# ProtectionChannelD.net
KiCad netlist of a schematic drawn in Altium Designer
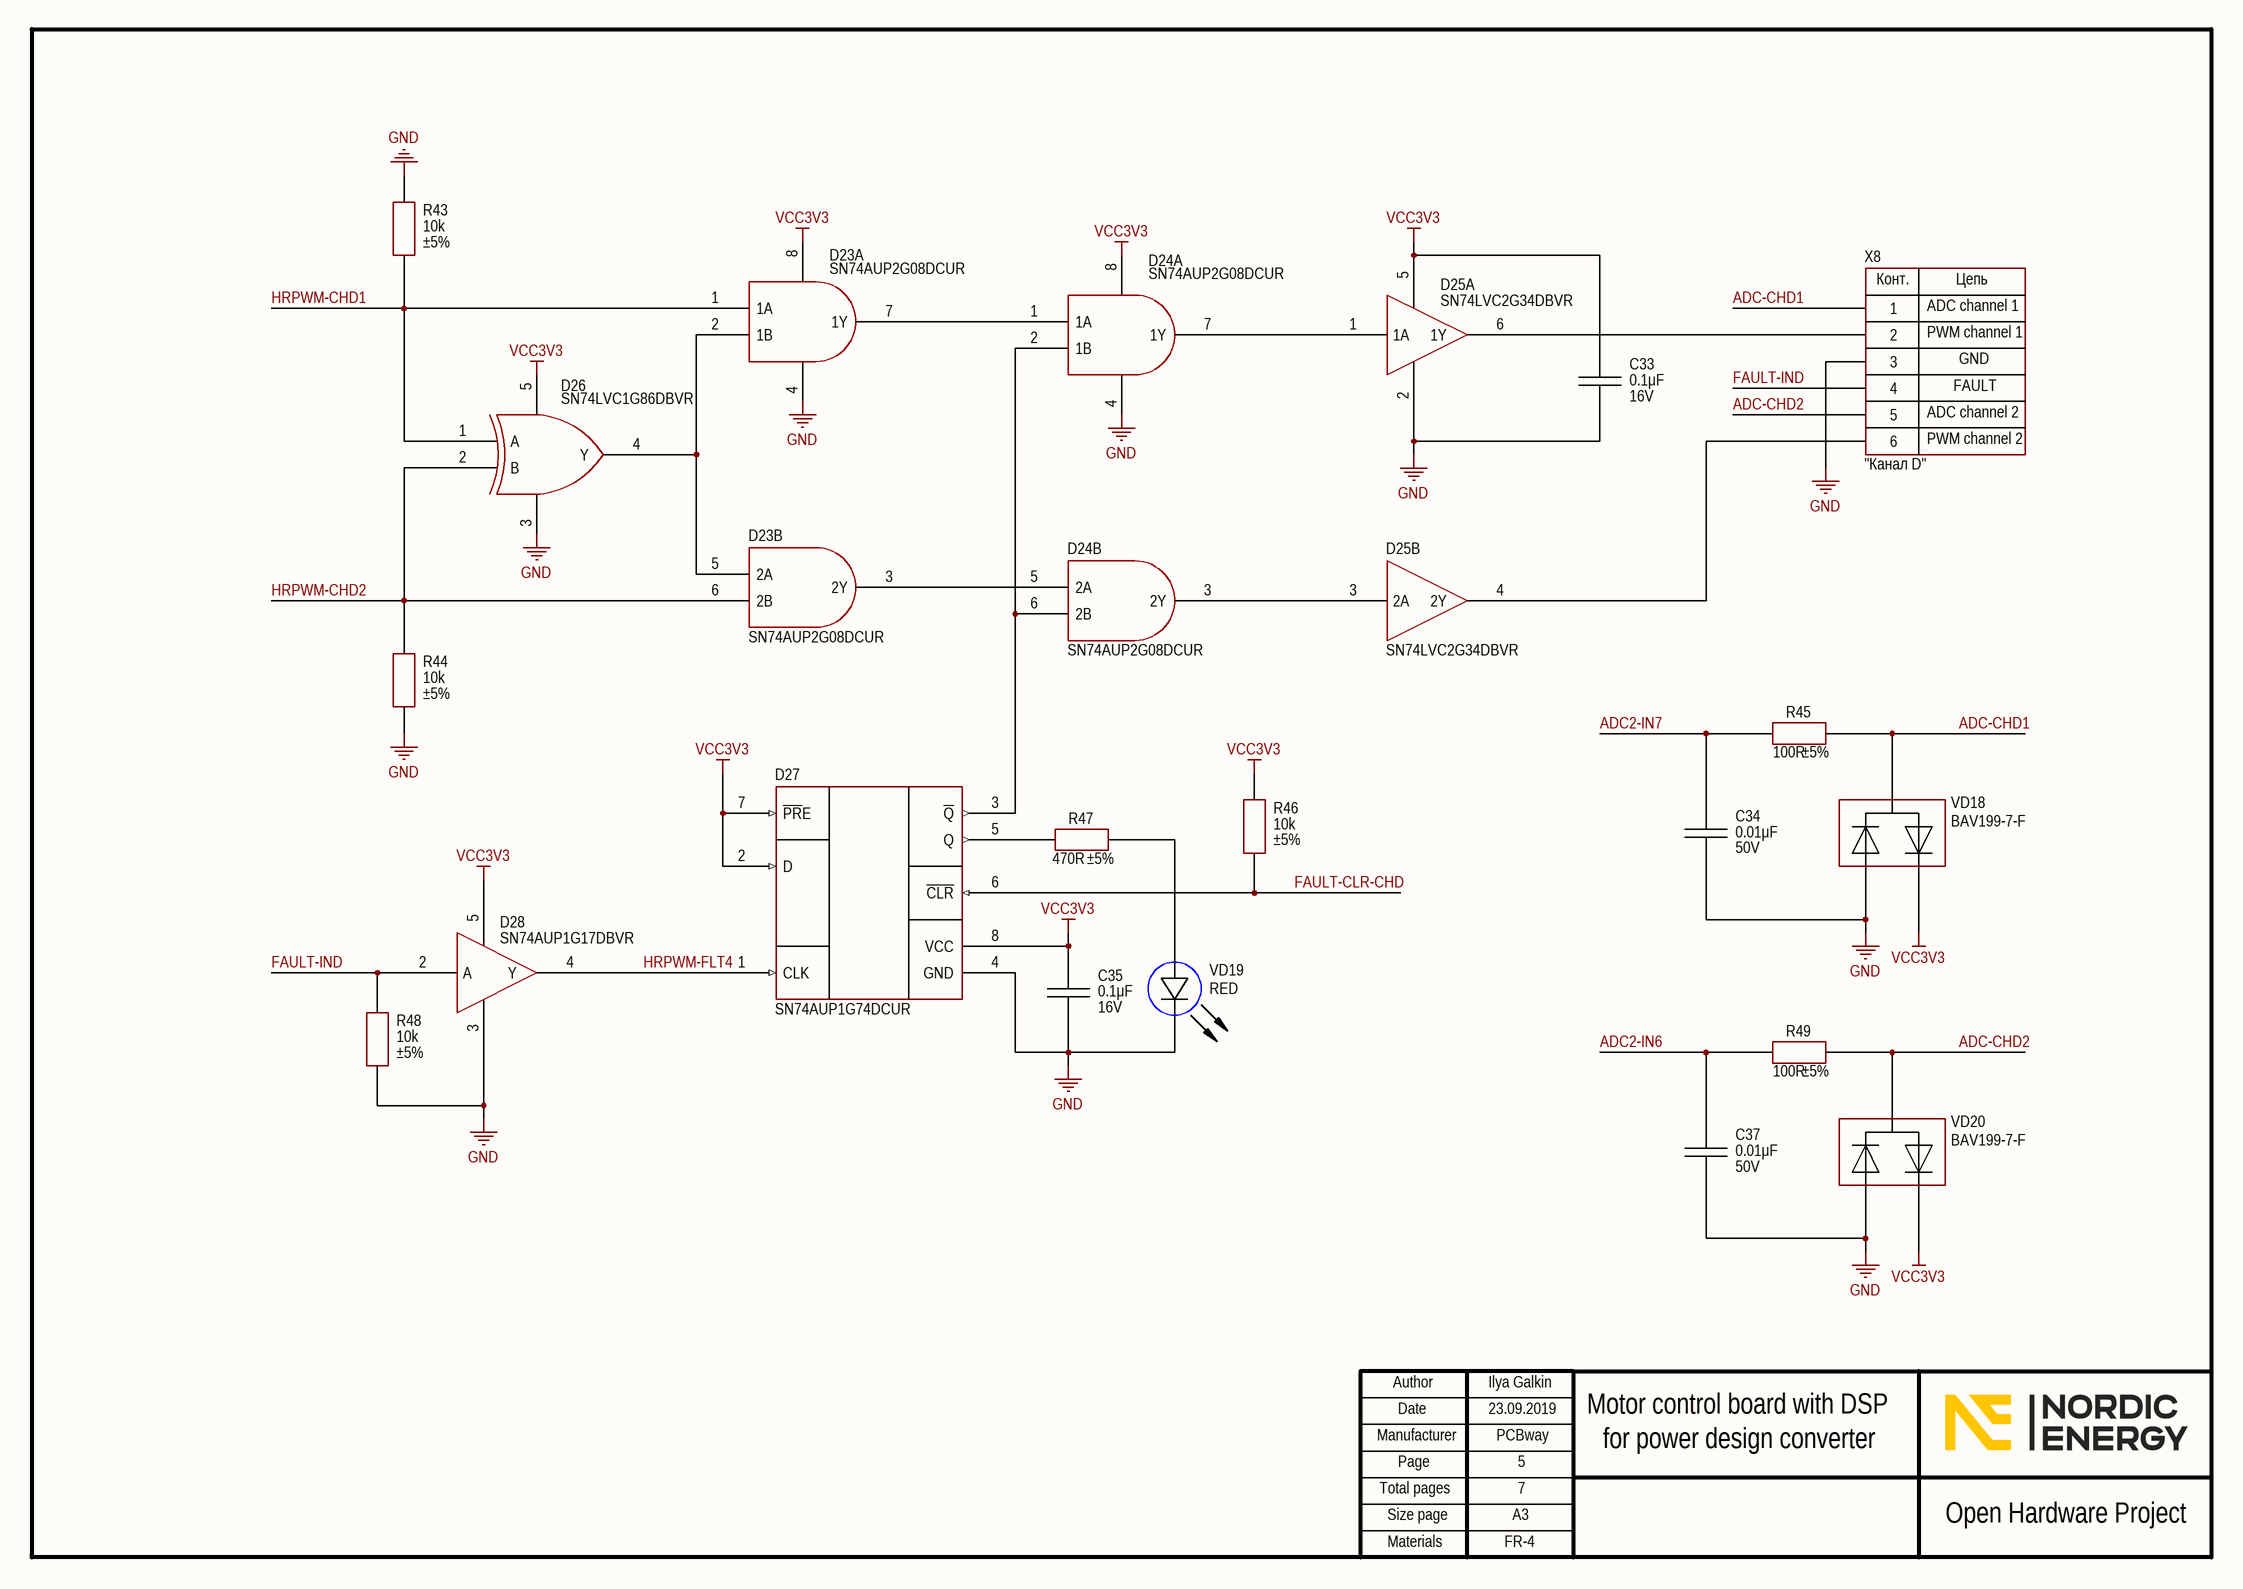
[diagram p0: ProtectionChannelD.SchDoc]

(export (version "E")
  (design (tool "Eeschema 10.0.6"))
  (components
    (comp (ref "C33")
      (value "0.1μF")
      (footprint "CAP: 0805")
      (fields
        (field (name "MANUFACTURER") "Yageo")
        (field (name "PARTNUMBER") "CC0805KRX7R7BB104")
        (field (name "VALUEMANUFACTURERPARTNUMBER") "Ceramic capacitor, 0.1μF, X7R, ±10%, 16V, 0805, -55...+125°C")
        (field (name "VOLTAGE") "16V")
      )
      (libsource (lib "Capacitor") (part "Ceramic_0805"))
    )
    (comp (ref "C34")
      (value "0.01μF")
      (footprint "CAP: 0805")
      (fields
        (field (name "MANUFACTURER") "Yageo")
        (field (name "PARTNUMBER") "CC0805KRX7R9BB103")
        (field (name "VALUEMANUFACTURERPARTNUMBER") "Ceramic capacitor, 0.01μF, X7R, ±10%, 50V, 0805, -55...+125°C")
        (field (name "VOLTAGE") "50V")
      )
      (libsource (lib "Capacitor") (part "Ceramic_0805"))
    )
    (comp (ref "C35")
      (value "0.1μF")
      (footprint "CAP: 0805")
      (fields
        (field (name "MANUFACTURER") "Yageo")
        (field (name "PARTNUMBER") "CC0805KRX7R7BB104")
        (field (name "VALUEMANUFACTURERPARTNUMBER") "Ceramic capacitor, 0.1μF, X7R, ±10%, 16V, 0805, -55...+125°C")
        (field (name "VOLTAGE") "16V")
      )
      (libsource (lib "Capacitor") (part "Ceramic_0805"))
    )
    (comp (ref "C37")
      (value "0.01μF")
      (footprint "CAP: 0805")
      (fields
        (field (name "MANUFACTURER") "Yageo")
        (field (name "PARTNUMBER") "CC0805KRX7R9BB103")
        (field (name "VALUEMANUFACTURERPARTNUMBER") "Ceramic capacitor, 0.01μF, X7R, ±10%, 50V, 0805, -55...+125°C")
        (field (name "VOLTAGE") "50V")
      )
      (libsource (lib "Capacitor") (part "Ceramic_0805"))
    )
    (comp (ref "D23")
      (value "~")
      (footprint "8-VSSOP")
      (description "AND")
      (fields
        (field (name "MANUFACTURER") "Texas Instruments")
        (field (name "VALUEMANUFACTURERPARTNUMBER") "IC logic AND, 0.8...3.6V, -40...+855°C, 8-VSSOP")
        (field (name "PARTNUMBER") "SN74AUP2G08DCUR")
      )
      (libsource (lib "IC. Logic") (part "SN74AUP2G08DCUR"))
    )
    (comp (ref "D24")
      (value "~")
      (footprint "8-VSSOP")
      (description "AND")
      (fields
        (field (name "MANUFACTURER") "Texas Instruments")
        (field (name "VALUEMANUFACTURERPARTNUMBER") "IC logic AND, 0.8...3.6V, -40...+855°C, 8-VSSOP")
        (field (name "PARTNUMBER") "SN74AUP2G08DCUR")
      )
      (libsource (lib "IC. Logic") (part "SN74AUP2G08DCUR"))
    )
    (comp (ref "D25")
      (value "~")
      (footprint "SOT23-6")
      (description "Buffer")
      (fields
        (field (name "MANUFACTURER") "Texas Instruments")
        (field (name "VALUEMANUFACTURERPARTNUMBER") "IC logic buffer, 1.65...5.5V, -40...+125°C, SOT23-6")
        (field (name "PARTNUMBER") "SN74LVC2G34DBVR")
      )
      (libsource (lib "IC. Logic") (part "SN74LVC2G34DBVR"))
    )
    (comp (ref "D26")
      (value "~")
      (footprint "SOT23-5")
      (description "XOR")
      (fields
        (field (name "MANUFACTURER") "Texas Instruments")
        (field (name "VALUEMANUFACTURERPARTNUMBER") "IC logic XOR, 1.65...5.5V, -40...+125°C, SOT23-5")
        (field (name "PARTNUMBER") "SN74LVC1G86DBVR")
      )
      (libsource (lib "IC. Logic") (part "SN74LVC1G86DBVR"))
    )
    (comp (ref "D27")
      (value "~")
      (footprint "8-VSSOP")
      (description "D-trigger")
      (fields
        (field (name "MANUFACTURER") "Texas Instruments")
        (field (name "VALUEMANUFACTURERPARTNUMBER") "ICtrigger D-type, 0.8...3.6V, -40...+85°C, 8-VSSOP")
        (field (name "PARTNUMBER") "SN74AUP1G74DCUR")
      )
      (libsource (lib "IC. Logic") (part "SN74AUP1G74DCUR"))
    )
    (comp (ref "D28")
      (value "~")
      (footprint "SOT23-5")
      (description "Schmitt trigger")
      (fields
        (field (name "MANUFACTURER") "Texas Instruments")
        (field (name "VALUEMANUFACTURERPARTNUMBER") "IC Schmitt trigger, 0.8...3.6V, -40...+85°C, SOT23-6")
        (field (name "PARTNUMBER") "SN74AUP1G17DBVR")
      )
      (libsource (lib "IC. Logic") (part "SN74AUP1G17DBVR"))
    )
    (comp (ref "R43")
      (value "10k")
      (footprint "RES: 0805")
      (fields
        (field (name "MANUFACTURER") "Yageo")
        (field (name "PARTNUMBER") "RC0805JR-0710KL")
        (field (name "VALUEMANUFACTURERPARTNUMBER") "Resistor film, 10k, ±5%, 0805, 0.125W, -55...+125°C")
        (field (name "TOLERANCE") "±5%")
      )
      (libsource (lib "Resistor") (part "Resistor_0805"))
    )
    (comp (ref "R44")
      (value "10k")
      (footprint "RES: 0805")
      (fields
        (field (name "MANUFACTURER") "Yageo")
        (field (name "PARTNUMBER") "RC0805JR-0710KL")
        (field (name "VALUEMANUFACTURERPARTNUMBER") "Resistor film, 10k, ±5%, 0805, 0.125W, -55...+125°C")
        (field (name "TOLERANCE") "±5%")
      )
      (libsource (lib "Resistor") (part "Resistor_0805"))
    )
    (comp (ref "R45")
      (value "100R")
      (footprint "RES: 0805")
      (fields
        (field (name "MANUFACTURER") "Yageo")
        (field (name "PARTNUMBER") "RC0805JR-07100RL")
        (field (name "VALUEMANUFACTURERPARTNUMBER") "Resistor film, 100R, ±5%, 0805, 0.125W, -55...+125°C")
        (field (name "TOLERANCE") "±5%")
      )
      (libsource (lib "") (part "Resistor_0805_1"))
    )
    (comp (ref "R46")
      (value "10k")
      (footprint "RES: 0805")
      (fields
        (field (name "MANUFACTURER") "Yageo")
        (field (name "PARTNUMBER") "RC0805JR-0710KL")
        (field (name "VALUEMANUFACTURERPARTNUMBER") "Resistor film, 10k, ±5%, 0805, 0.125W, -55...+125°C")
        (field (name "TOLERANCE") "±5%")
      )
      (libsource (lib "Resistor") (part "Resistor_0805"))
    )
    (comp (ref "R47")
      (value "470R")
      (footprint "RES: 0805")
      (fields
        (field (name "MANUFACTURER") "Yageo")
        (field (name "PARTNUMBER") "RC0805JR-07470RL")
        (field (name "VALUEMANUFACTURERPARTNUMBER") "Resistor film, 470R, ±5%, 0805, 0.125W, -55...+125°C")
        (field (name "TOLERANCE") "±5%")
      )
      (libsource (lib "") (part "Resistor_0805_2"))
    )
    (comp (ref "R48")
      (value "10k")
      (footprint "RES: 0805")
      (fields
        (field (name "MANUFACTURER") "Yageo")
        (field (name "PARTNUMBER") "RC0805JR-0710KL")
        (field (name "VALUEMANUFACTURERPARTNUMBER") "Resistor film, 10k, ±5%, 0805, 0.125W, -55...+125°C")
        (field (name "TOLERANCE") "±5%")
      )
      (libsource (lib "Resistor") (part "Resistor_0805"))
    )
    (comp (ref "R49")
      (value "100R")
      (footprint "RES: 0805")
      (fields
        (field (name "MANUFACTURER") "Yageo")
        (field (name "PARTNUMBER") "RC0805JR-07100RL")
        (field (name "VALUEMANUFACTURERPARTNUMBER") "Resistor film, 100R, ±5%, 0805, 0.125W, -55...+125°C")
        (field (name "TOLERANCE") "±5%")
      )
      (libsource (lib "") (part "Resistor_0805_1"))
    )
    (comp (ref "VD18")
      (value "~")
      (footprint "SOT23")
      (fields
        (field (name "MANUFACTURER") "Diodes Incorporated")
        (field (name "VALUEMANUFACTURERPARTNUMBER") "Diode array, 85V, 140mA, 1.1V, 3us, SOT-23, -65...+150°C")
        (field (name "VOLTAGE") "85V")
        (field (name "PARTNUMBER") "BAV199-7-F")
      )
      (libsource (lib "Diode") (part "Diode_array"))
    )
    (comp (ref "VD19")
      (value "~")
      (footprint "LED: 0805R")
      (fields
        (field (name "MANUFACTURER") "Wurth")
        (field (name "VALUEMANUFACTURERPARTNUMBER") "LED, 20mA, 2V, 0805, -55...+150°C")
        (field (name "PARTNUMBER") "150080RS75000")
        (field (name "COLOR") "RED")
      )
      (libsource (lib "Diode") (part "LED_single"))
    )
    (comp (ref "VD20")
      (value "~")
      (footprint "SOT23")
      (fields
        (field (name "MANUFACTURER") "Diodes Incorporated")
        (field (name "VALUEMANUFACTURERPARTNUMBER") "Diode array, 85V, 140mA, 1.1V, 3us, SOT-23, -65...+150°C")
        (field (name "VOLTAGE") "85V")
        (field (name "PARTNUMBER") "BAV199-7-F")
      )
      (libsource (lib "Diode") (part "Diode_array"))
    )
    (comp (ref "X8")
      (value "~")
      (footprint "CON: PLD-6")
      (fields
        (field (name "MANUFACTURER") "Connfly")
        (field (name "VALUEMANUFACTURERPARTNUMBER") "Connector, 6pin, 2.54mm, 500VAC, 3A")
        (field (name "PARTNUMBER") "PLD-6")
        (field (name "COMMENTTEXT") "\"Канал D\"")
      )
      (libsource (lib "Connector") (part "PLD-6"))
    )
  )
  (nets
    (net (code "1") (name "/ADC-CHD1") (class "Default")
      (node (ref "R45") (pin "2") (pinfunction "2_2") (pintype "passive"))
      (node (ref "VD18") (pin "3") (pinfunction "3_3") (pintype "passive"))
      (node (ref "X8") (pin "1") (pinfunction "1_1") (pintype "passive"))
    )
    (net (code "2") (name "/ADC-CHD2") (class "Default")
      (node (ref "R49") (pin "2") (pinfunction "2_2") (pintype "passive"))
      (node (ref "VD20") (pin "3") (pinfunction "3_3") (pintype "passive"))
      (node (ref "X8") (pin "5") (pinfunction "5_5") (pintype "power_in"))
    )
    (net (code "3") (name "/ADC2-IN6") (class "Default")
      (node (ref "C37") (pin "2") (pinfunction "2_2") (pintype "power_in"))
      (node (ref "R49") (pin "1") (pinfunction "1_1") (pintype "passive"))
    )
    (net (code "4") (name "/ADC2-IN7") (class "Default")
      (node (ref "C34") (pin "2") (pinfunction "2_2") (pintype "power_in"))
      (node (ref "R45") (pin "1") (pinfunction "1_1") (pintype "passive"))
    )
    (net (code "5") (name "/FAULT-CLR-CHD") (class "Default")
      (node (ref "D27") (pin "6") (pinfunction "~{CLR}_6") (pintype "input"))
      (node (ref "R46") (pin "2") (pinfunction "2_2") (pintype "passive"))
    )
    (net (code "6") (name "/FAULT-IND") (class "Default")
      (node (ref "D28") (pin "2") (pinfunction "A_2") (pintype "passive"))
      (node (ref "R48") (pin "1") (pinfunction "1_1") (pintype "passive"))
      (node (ref "X8") (pin "4") (pinfunction "4_4") (pintype "power_in"))
    )
    (net (code "7") (name "/HRPWM-CHD1") (class "Default")
      (node (ref "D23") (pin "1") (pinfunction "1A_1") (pintype "passive"))
      (node (ref "D26") (pin "1") (pinfunction "A_1") (pintype "passive"))
      (node (ref "R43") (pin "2") (pinfunction "2_2") (pintype "passive"))
    )
    (net (code "8") (name "/HRPWM-CHD2") (class "Default")
      (node (ref "D23") (pin "6") (pinfunction "2B_6") (pintype "passive"))
      (node (ref "D26") (pin "2") (pinfunction "B_2") (pintype "passive"))
      (node (ref "R44") (pin "1") (pinfunction "1_1") (pintype "passive"))
    )
    (net (code "9") (name "/HRPWM-FLT4") (class "Default")
      (node (ref "D27") (pin "1") (pinfunction "CLK_1") (pintype "input"))
      (node (ref "D28") (pin "4") (pinfunction "Y_4") (pintype "passive"))
    )
    (net (code "10") (name "GND") (class "Default")
      (node (ref "C33") (pin "1") (pinfunction "1_1") (pintype "power_in"))
      (node (ref "C34") (pin "1") (pinfunction "1_1") (pintype "power_in"))
      (node (ref "C35") (pin "1") (pinfunction "1_1") (pintype "power_in"))
      (node (ref "C37") (pin "1") (pinfunction "1_1") (pintype "power_in"))
      (node (ref "D23") (pin "4") (pintype "passive"))
      (node (ref "D24") (pin "4") (pintype "passive"))
      (node (ref "D25") (pin "2") (pintype "passive"))
      (node (ref "D26") (pin "3") (pintype "passive"))
      (node (ref "D27") (pin "4") (pinfunction "GND_4") (pintype "passive"))
      (node (ref "D28") (pin "3") (pintype "passive"))
      (node (ref "R43") (pin "1") (pinfunction "1_1") (pintype "passive"))
      (node (ref "R44") (pin "2") (pinfunction "2_2") (pintype "passive"))
      (node (ref "R48") (pin "2") (pinfunction "2_2") (pintype "passive"))
      (node (ref "VD18") (pin "1") (pinfunction "1_1") (pintype "passive"))
      (node (ref "VD19") (pin "2") (pinfunction "C_2") (pintype "passive"))
      (node (ref "VD20") (pin "1") (pinfunction "1_1") (pintype "passive"))
      (node (ref "X8") (pin "3") (pinfunction "3_3") (pintype "power_in"))
    )
    (net (code "11") (name "Net-(D23A-1B)") (class "Default")
      (node (ref "D23") (pin "2") (pinfunction "1B_2") (pintype "passive"))
      (node (ref "D23") (pin "5") (pinfunction "2A_5") (pintype "passive"))
      (node (ref "D26") (pin "4") (pinfunction "Y_4") (pintype "passive"))
    )
    (net (code "12") (name "Net-(D23A-1Y)") (class "Default")
      (node (ref "D23") (pin "7") (pinfunction "1Y_7") (pintype "passive"))
      (node (ref "D24") (pin "1") (pinfunction "1A_1") (pintype "passive"))
    )
    (net (code "13") (name "Net-(D23B-2Y)") (class "Default")
      (node (ref "D23") (pin "3") (pinfunction "2Y_3") (pintype "passive"))
      (node (ref "D24") (pin "5") (pinfunction "2A_5") (pintype "passive"))
    )
    (net (code "14") (name "Net-(D24A-1B)") (class "Default")
      (node (ref "D24") (pin "2") (pinfunction "1B_2") (pintype "passive"))
      (node (ref "D24") (pin "6") (pinfunction "2B_6") (pintype "passive"))
      (node (ref "D27") (pin "3") (pinfunction "~{Q}_3") (pintype "output"))
    )
    (net (code "15") (name "Net-(D24A-1Y)") (class "Default")
      (node (ref "D24") (pin "7") (pinfunction "1Y_7") (pintype "passive"))
      (node (ref "D25") (pin "1") (pinfunction "1A_1") (pintype "passive"))
    )
    (net (code "16") (name "Net-(D24B-2Y)") (class "Default")
      (node (ref "D24") (pin "3") (pinfunction "2Y_3") (pintype "passive"))
      (node (ref "D25") (pin "3") (pinfunction "2A_3") (pintype "passive"))
    )
    (net (code "17") (name "Net-(D25A-1Y)") (class "Default")
      (node (ref "D25") (pin "6") (pinfunction "1Y_6") (pintype "passive"))
      (node (ref "X8") (pin "2") (pinfunction "2_2") (pintype "passive"))
    )
    (net (code "18") (name "Net-(D25B-2Y)") (class "Default")
      (node (ref "D25") (pin "4") (pinfunction "2Y_4") (pintype "passive"))
      (node (ref "X8") (pin "6") (pinfunction "6_6") (pintype "power_in"))
    )
    (net (code "19") (name "Net-(D27-Q)") (class "Default")
      (node (ref "D27") (pin "5") (pinfunction "Q_5") (pintype "output"))
      (node (ref "R47") (pin "2") (pinfunction "2_2") (pintype "passive"))
    )
    (net (code "20") (name "Net-(VD19-A)") (class "Default")
      (node (ref "R47") (pin "1") (pinfunction "1_1") (pintype "passive"))
      (node (ref "VD19") (pin "1") (pinfunction "A_1") (pintype "passive"))
    )
    (net (code "21") (name "VCC3V3") (class "Default")
      (node (ref "C33") (pin "2") (pinfunction "2_2") (pintype "power_in"))
      (node (ref "C35") (pin "2") (pinfunction "2_2") (pintype "power_in"))
      (node (ref "D23") (pin "8") (pintype "passive"))
      (node (ref "D24") (pin "8") (pintype "passive"))
      (node (ref "D25") (pin "5") (pintype "passive"))
      (node (ref "D26") (pin "5") (pintype "passive"))
      (node (ref "D27") (pin "2") (pinfunction "D_2") (pintype "input"))
      (node (ref "D27") (pin "7") (pinfunction "~{PR}E_7") (pintype "input"))
      (node (ref "D27") (pin "8") (pinfunction "VCC_8") (pintype "passive"))
      (node (ref "D28") (pin "5") (pintype "passive"))
      (node (ref "R46") (pin "1") (pinfunction "1_1") (pintype "passive"))
      (node (ref "VD18") (pin "2") (pinfunction "2_2") (pintype "passive"))
      (node (ref "VD20") (pin "2") (pinfunction "2_2") (pintype "passive"))
    )
  )
)
